# IX01.net
KiCad netlist of a schematic drawn in EAGLE
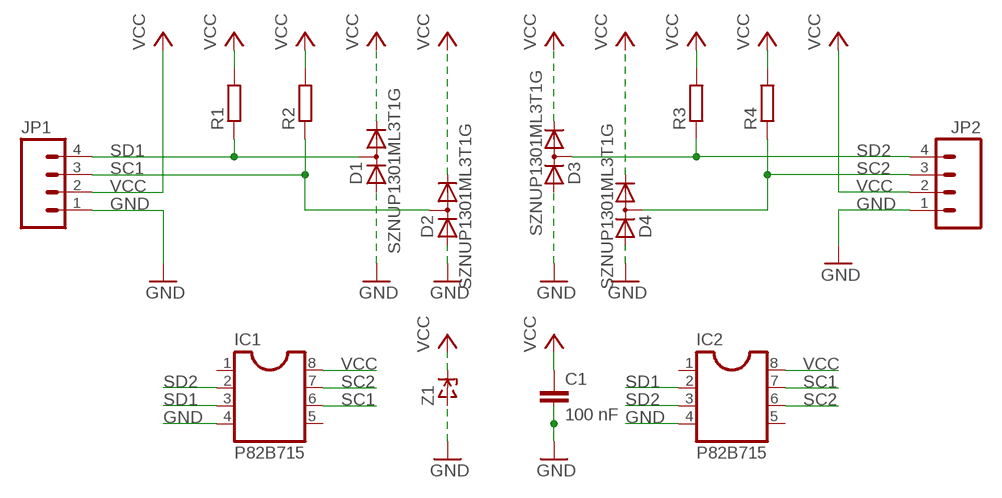
[diagram p0: schematic, sheet 1]

(export (version "E")
  (design (tool "Eeschema 10.0.6"))
  (components
    (comp (ref "C1")
      (value "100 nF")
      (footprint "eagle-import:C0805")
      (libsource (lib "eagle-import") (part "C-EUC0805"))
    )
    (comp (ref "D1")
      (value "SZNUP1301ML3T1G")
      (footprint "eagle-import:SOT23")
      (libsource (lib "eagle-import") (part "BAV199"))
    )
    (comp (ref "D2")
      (value "SZNUP1301ML3T1G")
      (footprint "eagle-import:SOT23")
      (libsource (lib "eagle-import") (part "BAV199"))
    )
    (comp (ref "D3")
      (value "SZNUP1301ML3T1G")
      (footprint "eagle-import:SOT23")
      (libsource (lib "eagle-import") (part "BAV199"))
    )
    (comp (ref "D4")
      (value "SZNUP1301ML3T1G")
      (footprint "eagle-import:SOT23")
      (libsource (lib "eagle-import") (part "BAV199"))
    )
    (comp (ref "IC1")
      (value "P82B715")
      (footprint "eagle-import:SO-8")
      (libsource (lib "eagle-import") (part "IC_DIL8-SO8"))
    )
    (comp (ref "IC2")
      (value "P82B715")
      (footprint "eagle-import:SO-8")
      (libsource (lib "eagle-import") (part "IC_DIL8-SO8"))
    )
    (comp (ref "JP1")
      (value "M04PTH")
      (footprint "eagle-import:1X04")
      (libsource (lib "eagle-import") (part "M04PTH"))
    )
    (comp (ref "JP2")
      (value "M04PTH")
      (footprint "eagle-import:1X04")
      (libsource (lib "eagle-import") (part "M04PTH"))
    )
    (comp (ref "R1")
      (value "R-EU_R0805")
      (footprint "eagle-import:R0805")
      (libsource (lib "eagle-import") (part "R-EU_R0805"))
    )
    (comp (ref "R2")
      (value "R-EU_R0805")
      (footprint "eagle-import:R0805")
      (libsource (lib "eagle-import") (part "R-EU_R0805"))
    )
    (comp (ref "R3")
      (value "R-EU_R0805")
      (footprint "eagle-import:R0805")
      (libsource (lib "eagle-import") (part "R-EU_R0805"))
    )
    (comp (ref "R4")
      (value "R-EU_R0805")
      (footprint "eagle-import:R0805")
      (libsource (lib "eagle-import") (part "R-EU_R0805"))
    )
    (comp (ref "Z1")
      (value "ZENERSOD-323F")
      (footprint "eagle-import:SOD-323F")
      (libsource (lib "eagle-import") (part "ZENERSOD-323F"))
    )
  )
  (nets
    (net (code "1") (name "/SC1") (class "Default")
      (node (ref "D2") (pin "3") (pinfunction "AC_3") (pintype "passive"))
      (node (ref "IC1") (pin "6") (pinfunction "6_6") (pintype "bidirectional"))
      (node (ref "IC2") (pin "7") (pinfunction "7_7") (pintype "bidirectional"))
      (node (ref "JP1") (pin "3") (pinfunction "3_3") (pintype "passive"))
      (node (ref "R2") (pin "1") (pinfunction "1_1") (pintype "passive"))
    )
    (net (code "2") (name "/SC2") (class "Default")
      (node (ref "D4") (pin "3") (pinfunction "AC_3") (pintype "passive"))
      (node (ref "IC1") (pin "7") (pinfunction "7_7") (pintype "bidirectional"))
      (node (ref "IC2") (pin "6") (pinfunction "6_6") (pintype "bidirectional"))
      (node (ref "JP2") (pin "3") (pinfunction "3_3") (pintype "passive"))
      (node (ref "R4") (pin "1") (pinfunction "1_1") (pintype "passive"))
    )
    (net (code "3") (name "/SD1") (class "Default")
      (node (ref "D1") (pin "3") (pinfunction "AC_3") (pintype "passive"))
      (node (ref "IC1") (pin "3") (pinfunction "3_3") (pintype "bidirectional"))
      (node (ref "IC2") (pin "2") (pinfunction "2_2") (pintype "bidirectional"))
      (node (ref "JP1") (pin "4") (pinfunction "4_4") (pintype "passive"))
      (node (ref "R1") (pin "1") (pinfunction "1_1") (pintype "passive"))
    )
    (net (code "4") (name "/SD2") (class "Default")
      (node (ref "D3") (pin "3") (pinfunction "AC_3") (pintype "passive"))
      (node (ref "IC1") (pin "2") (pinfunction "2_2") (pintype "bidirectional"))
      (node (ref "IC2") (pin "3") (pinfunction "3_3") (pintype "bidirectional"))
      (node (ref "JP2") (pin "4") (pinfunction "4_4") (pintype "passive"))
      (node (ref "R3") (pin "1") (pinfunction "1_1") (pintype "passive"))
    )
    (net (code "5") (name "GND") (class "Default")
      (node (ref "C1") (pin "2") (pinfunction "2_2") (pintype "passive"))
      (node (ref "D1") (pin "1") (pinfunction "A_1") (pintype "passive"))
      (node (ref "D2") (pin "1") (pinfunction "A_1") (pintype "passive"))
      (node (ref "D3") (pin "1") (pinfunction "A_1") (pintype "passive"))
      (node (ref "D4") (pin "1") (pinfunction "A_1") (pintype "passive"))
      (node (ref "IC1") (pin "4") (pinfunction "4_4") (pintype "bidirectional"))
      (node (ref "IC2") (pin "4") (pinfunction "4_4") (pintype "bidirectional"))
      (node (ref "JP1") (pin "1") (pinfunction "1_1") (pintype "passive"))
      (node (ref "JP2") (pin "1") (pinfunction "1_1") (pintype "passive"))
      (node (ref "Z1") (pin "A") (pinfunction "A_A") (pintype "passive"))
    )
    (net (code "6") (name "VCC") (class "Default")
      (node (ref "C1") (pin "1") (pinfunction "1_1") (pintype "passive"))
      (node (ref "D1") (pin "2") (pinfunction "C_2") (pintype "passive"))
      (node (ref "D2") (pin "2") (pinfunction "C_2") (pintype "passive"))
      (node (ref "D3") (pin "2") (pinfunction "C_2") (pintype "passive"))
      (node (ref "D4") (pin "2") (pinfunction "C_2") (pintype "passive"))
      (node (ref "IC1") (pin "8") (pinfunction "8_8") (pintype "bidirectional"))
      (node (ref "IC2") (pin "8") (pinfunction "8_8") (pintype "bidirectional"))
      (node (ref "JP1") (pin "2") (pinfunction "2_2") (pintype "passive"))
      (node (ref "JP2") (pin "2") (pinfunction "2_2") (pintype "passive"))
      (node (ref "R1") (pin "2") (pinfunction "2_2") (pintype "passive"))
      (node (ref "R2") (pin "2") (pinfunction "2_2") (pintype "passive"))
      (node (ref "R3") (pin "2") (pinfunction "2_2") (pintype "passive"))
      (node (ref "R4") (pin "2") (pinfunction "2_2") (pintype "passive"))
      (node (ref "Z1") (pin "C") (pinfunction "C_C") (pintype "passive"))
    )
    (net (code "7") (name "unconnected-(IC1-Pad1)") (class "Default")
      (node (ref "IC1") (pin "1") (pinfunction "1_1") (pintype "bidirectional"))
    )
    (net (code "8") (name "unconnected-(IC1-Pad5)") (class "Default")
      (node (ref "IC1") (pin "5") (pinfunction "5_5") (pintype "bidirectional"))
    )
    (net (code "9") (name "unconnected-(IC2-Pad1)") (class "Default")
      (node (ref "IC2") (pin "1") (pinfunction "1_1") (pintype "bidirectional"))
    )
    (net (code "10") (name "unconnected-(IC2-Pad5)") (class "Default")
      (node (ref "IC2") (pin "5") (pinfunction "5_5") (pintype "bidirectional"))
    )
  )
)
